# v001.net
KiCad netlist of a schematic drawn in EAGLE
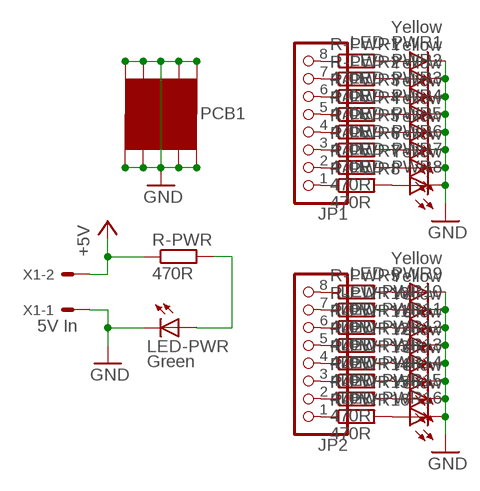
[diagram p0: schematic, sheet 1]

(export (version "E")
  (design (tool "Eeschema 10.0.6"))
  (components
    (comp (ref "JP1")
      (value "PINHD-1X8")
      (footprint "eagle-import:1X08")
      (libsource (lib "eagle-import") (part "PINHD-1X8"))
    )
    (comp (ref "JP2")
      (value "PINHD-1X8")
      (footprint "eagle-import:1X08")
      (libsource (lib "eagle-import") (part "PINHD-1X8"))
    )
    (comp (ref "LED-PWR")
      (value "Green")
      (footprint "eagle-import:LED3MM")
      (libsource (lib "eagle-import") (part "LED3MM"))
    )
    (comp (ref "LED-PWR1")
      (value "Yellow")
      (footprint "eagle-import:LED3MM")
      (libsource (lib "eagle-import") (part "LED3MM"))
    )
    (comp (ref "LED-PWR2")
      (value "Yellow")
      (footprint "eagle-import:LED3MM")
      (libsource (lib "eagle-import") (part "LED3MM"))
    )
    (comp (ref "LED-PWR3")
      (value "Yellow")
      (footprint "eagle-import:LED3MM")
      (libsource (lib "eagle-import") (part "LED3MM"))
    )
    (comp (ref "LED-PWR4")
      (value "Yellow")
      (footprint "eagle-import:LED3MM")
      (libsource (lib "eagle-import") (part "LED3MM"))
    )
    (comp (ref "LED-PWR5")
      (value "Yellow")
      (footprint "eagle-import:LED3MM")
      (libsource (lib "eagle-import") (part "LED3MM"))
    )
    (comp (ref "LED-PWR6")
      (value "Yellow")
      (footprint "eagle-import:LED3MM")
      (libsource (lib "eagle-import") (part "LED3MM"))
    )
    (comp (ref "LED-PWR7")
      (value "Yellow")
      (footprint "eagle-import:LED3MM")
      (libsource (lib "eagle-import") (part "LED3MM"))
    )
    (comp (ref "LED-PWR8")
      (value "Yellow")
      (footprint "eagle-import:LED3MM")
      (libsource (lib "eagle-import") (part "LED3MM"))
    )
    (comp (ref "LED-PWR9")
      (value "Yellow")
      (footprint "eagle-import:LED3MM")
      (libsource (lib "eagle-import") (part "LED3MM"))
    )
    (comp (ref "LED-PWR10")
      (value "Yellow")
      (footprint "eagle-import:LED3MM")
      (libsource (lib "eagle-import") (part "LED3MM"))
    )
    (comp (ref "LED-PWR11")
      (value "Yellow")
      (footprint "eagle-import:LED3MM")
      (libsource (lib "eagle-import") (part "LED3MM"))
    )
    (comp (ref "LED-PWR12")
      (value "Yellow")
      (footprint "eagle-import:LED3MM")
      (libsource (lib "eagle-import") (part "LED3MM"))
    )
    (comp (ref "LED-PWR13")
      (value "Yellow")
      (footprint "eagle-import:LED3MM")
      (libsource (lib "eagle-import") (part "LED3MM"))
    )
    (comp (ref "LED-PWR14")
      (value "Yellow")
      (footprint "eagle-import:LED3MM")
      (libsource (lib "eagle-import") (part "LED3MM"))
    )
    (comp (ref "LED-PWR15")
      (value "Yellow")
      (footprint "eagle-import:LED3MM")
      (libsource (lib "eagle-import") (part "LED3MM"))
    )
    (comp (ref "LED-PWR16")
      (value "Yellow")
      (footprint "eagle-import:LED3MM")
      (libsource (lib "eagle-import") (part "LED3MM"))
    )
    (comp (ref "PCB1")
      (value "PCB05X05")
      (footprint "eagle-import:PCB_05X05")
      (libsource (lib "eagle-import") (part "PCB05X05"))
    )
    (comp (ref "R-PWR")
      (value "470R")
      (footprint "eagle-import:0204_7")
      (libsource (lib "eagle-import") (part "R-EU_0204/7"))
    )
    (comp (ref "R-PWR1")
      (value "470R")
      (footprint "eagle-import:0204_7")
      (libsource (lib "eagle-import") (part "R-EU_0204/7"))
    )
    (comp (ref "R-PWR2")
      (value "470R")
      (footprint "eagle-import:0204_7")
      (libsource (lib "eagle-import") (part "R-EU_0204/7"))
    )
    (comp (ref "R-PWR3")
      (value "470R")
      (footprint "eagle-import:0204_7")
      (libsource (lib "eagle-import") (part "R-EU_0204/7"))
    )
    (comp (ref "R-PWR4")
      (value "470R")
      (footprint "eagle-import:0204_7")
      (libsource (lib "eagle-import") (part "R-EU_0204/7"))
    )
    (comp (ref "R-PWR5")
      (value "470R")
      (footprint "eagle-import:0204_7")
      (libsource (lib "eagle-import") (part "R-EU_0204/7"))
    )
    (comp (ref "R-PWR6")
      (value "470R")
      (footprint "eagle-import:0204_7")
      (libsource (lib "eagle-import") (part "R-EU_0204/7"))
    )
    (comp (ref "R-PWR7")
      (value "470R")
      (footprint "eagle-import:0204_7")
      (libsource (lib "eagle-import") (part "R-EU_0204/7"))
    )
    (comp (ref "R-PWR8")
      (value "470R")
      (footprint "eagle-import:0204_7")
      (libsource (lib "eagle-import") (part "R-EU_0204/7"))
    )
    (comp (ref "R-PWR9")
      (value "470R")
      (footprint "eagle-import:0204_7")
      (libsource (lib "eagle-import") (part "R-EU_0204/7"))
    )
    (comp (ref "R-PWR10")
      (value "470R")
      (footprint "eagle-import:0204_7")
      (libsource (lib "eagle-import") (part "R-EU_0204/7"))
    )
    (comp (ref "R-PWR11")
      (value "470R")
      (footprint "eagle-import:0204_7")
      (libsource (lib "eagle-import") (part "R-EU_0204/7"))
    )
    (comp (ref "R-PWR12")
      (value "470R")
      (footprint "eagle-import:0204_7")
      (libsource (lib "eagle-import") (part "R-EU_0204/7"))
    )
    (comp (ref "R-PWR13")
      (value "470R")
      (footprint "eagle-import:0204_7")
      (libsource (lib "eagle-import") (part "R-EU_0204/7"))
    )
    (comp (ref "R-PWR14")
      (value "470R")
      (footprint "eagle-import:0204_7")
      (libsource (lib "eagle-import") (part "R-EU_0204/7"))
    )
    (comp (ref "R-PWR15")
      (value "470R")
      (footprint "eagle-import:0204_7")
      (libsource (lib "eagle-import") (part "R-EU_0204/7"))
    )
    (comp (ref "R-PWR16")
      (value "470R")
      (footprint "eagle-import:0204_7")
      (libsource (lib "eagle-import") (part "R-EU_0204/7"))
    )
    (comp (ref "X1")
      (value "5V In")
      (footprint "eagle-import:6410-02")
      (libsource (lib "eagle-import") (part "22-?-0227-2021"))
    )
  )
  (nets
    (net (code "1") (name "+5V") (class "Default")
      (node (ref "R-PWR") (pin "1") (pinfunction "1_1") (pintype "passive"))
      (node (ref "X1") (pin "2") (pinfunction "S_2") (pintype "passive"))
    )
    (net (code "2") (name "GND") (class "Default")
      (node (ref "LED-PWR") (pin "K") (pinfunction "C_K") (pintype "passive"))
      (node (ref "LED-PWR1") (pin "K") (pinfunction "C_K") (pintype "passive"))
      (node (ref "LED-PWR10") (pin "K") (pinfunction "C_K") (pintype "passive"))
      (node (ref "LED-PWR11") (pin "K") (pinfunction "C_K") (pintype "passive"))
      (node (ref "LED-PWR12") (pin "K") (pinfunction "C_K") (pintype "passive"))
      (node (ref "LED-PWR13") (pin "K") (pinfunction "C_K") (pintype "passive"))
      (node (ref "LED-PWR14") (pin "K") (pinfunction "C_K") (pintype "passive"))
      (node (ref "LED-PWR15") (pin "K") (pinfunction "C_K") (pintype "passive"))
      (node (ref "LED-PWR16") (pin "K") (pinfunction "C_K") (pintype "passive"))
      (node (ref "LED-PWR2") (pin "K") (pinfunction "C_K") (pintype "passive"))
      (node (ref "LED-PWR3") (pin "K") (pinfunction "C_K") (pintype "passive"))
      (node (ref "LED-PWR4") (pin "K") (pinfunction "C_K") (pintype "passive"))
      (node (ref "LED-PWR5") (pin "K") (pinfunction "C_K") (pintype "passive"))
      (node (ref "LED-PWR6") (pin "K") (pinfunction "C_K") (pintype "passive"))
      (node (ref "LED-PWR7") (pin "K") (pinfunction "C_K") (pintype "passive"))
      (node (ref "LED-PWR8") (pin "K") (pinfunction "C_K") (pintype "passive"))
      (node (ref "LED-PWR9") (pin "K") (pinfunction "C_K") (pintype "passive"))
      (node (ref "PCB1") (pin "GND@1") (pinfunction "GND_GND@1") (pintype "bidirectional"))
      (node (ref "PCB1") (pin "GND@2") (pinfunction "GND_GND@2") (pintype "bidirectional"))
      (node (ref "PCB1") (pin "GND@3") (pinfunction "GND_GND@3") (pintype "bidirectional"))
      (node (ref "PCB1") (pin "GND@4") (pinfunction "GND_GND@4") (pintype "bidirectional"))
      (node (ref "PCB1") (pin "GND@5") (pinfunction "GND_GND@5") (pintype "bidirectional"))
      (node (ref "PCB1") (pin "GND@6") (pinfunction "GND_GND@6") (pintype "bidirectional"))
      (node (ref "PCB1") (pin "GND@7") (pinfunction "GND_GND@7") (pintype "bidirectional"))
      (node (ref "PCB1") (pin "GND@8") (pinfunction "GND_GND@8") (pintype "bidirectional"))
      (node (ref "X1") (pin "1") (pinfunction "S_1") (pintype "passive"))
    )
    (net (code "3") (name "Net-(JP1-Pad1)") (class "Default")
      (node (ref "JP1") (pin "1") (pinfunction "1_1") (pintype "passive"))
      (node (ref "R-PWR8") (pin "1") (pinfunction "1_1") (pintype "passive"))
    )
    (net (code "4") (name "Net-(JP1-Pad2)") (class "Default")
      (node (ref "JP1") (pin "2") (pinfunction "2_2") (pintype "passive"))
      (node (ref "R-PWR7") (pin "1") (pinfunction "1_1") (pintype "passive"))
    )
    (net (code "5") (name "Net-(JP1-Pad3)") (class "Default")
      (node (ref "JP1") (pin "3") (pinfunction "3_3") (pintype "passive"))
      (node (ref "R-PWR6") (pin "1") (pinfunction "1_1") (pintype "passive"))
    )
    (net (code "6") (name "Net-(JP1-Pad4)") (class "Default")
      (node (ref "JP1") (pin "4") (pinfunction "4_4") (pintype "passive"))
      (node (ref "R-PWR5") (pin "1") (pinfunction "1_1") (pintype "passive"))
    )
    (net (code "7") (name "Net-(JP1-Pad5)") (class "Default")
      (node (ref "JP1") (pin "5") (pinfunction "5_5") (pintype "passive"))
      (node (ref "R-PWR4") (pin "1") (pinfunction "1_1") (pintype "passive"))
    )
    (net (code "8") (name "Net-(JP1-Pad6)") (class "Default")
      (node (ref "JP1") (pin "6") (pinfunction "6_6") (pintype "passive"))
      (node (ref "R-PWR3") (pin "1") (pinfunction "1_1") (pintype "passive"))
    )
    (net (code "9") (name "Net-(JP1-Pad7)") (class "Default")
      (node (ref "JP1") (pin "7") (pinfunction "7_7") (pintype "passive"))
      (node (ref "R-PWR2") (pin "1") (pinfunction "1_1") (pintype "passive"))
    )
    (net (code "10") (name "Net-(JP1-Pad8)") (class "Default")
      (node (ref "JP1") (pin "8") (pinfunction "8_8") (pintype "passive"))
      (node (ref "R-PWR1") (pin "1") (pinfunction "1_1") (pintype "passive"))
    )
    (net (code "11") (name "Net-(JP2-Pad1)") (class "Default")
      (node (ref "JP2") (pin "1") (pinfunction "1_1") (pintype "passive"))
      (node (ref "R-PWR16") (pin "1") (pinfunction "1_1") (pintype "passive"))
    )
    (net (code "12") (name "Net-(JP2-Pad2)") (class "Default")
      (node (ref "JP2") (pin "2") (pinfunction "2_2") (pintype "passive"))
      (node (ref "R-PWR15") (pin "1") (pinfunction "1_1") (pintype "passive"))
    )
    (net (code "13") (name "Net-(JP2-Pad3)") (class "Default")
      (node (ref "JP2") (pin "3") (pinfunction "3_3") (pintype "passive"))
      (node (ref "R-PWR14") (pin "1") (pinfunction "1_1") (pintype "passive"))
    )
    (net (code "14") (name "Net-(JP2-Pad4)") (class "Default")
      (node (ref "JP2") (pin "4") (pinfunction "4_4") (pintype "passive"))
      (node (ref "R-PWR13") (pin "1") (pinfunction "1_1") (pintype "passive"))
    )
    (net (code "15") (name "Net-(JP2-Pad5)") (class "Default")
      (node (ref "JP2") (pin "5") (pinfunction "5_5") (pintype "passive"))
      (node (ref "R-PWR12") (pin "1") (pinfunction "1_1") (pintype "passive"))
    )
    (net (code "16") (name "Net-(JP2-Pad6)") (class "Default")
      (node (ref "JP2") (pin "6") (pinfunction "6_6") (pintype "passive"))
      (node (ref "R-PWR11") (pin "1") (pinfunction "1_1") (pintype "passive"))
    )
    (net (code "17") (name "Net-(JP2-Pad7)") (class "Default")
      (node (ref "JP2") (pin "7") (pinfunction "7_7") (pintype "passive"))
      (node (ref "R-PWR10") (pin "1") (pinfunction "1_1") (pintype "passive"))
    )
    (net (code "18") (name "Net-(JP2-Pad8)") (class "Default")
      (node (ref "JP2") (pin "8") (pinfunction "8_8") (pintype "passive"))
      (node (ref "R-PWR9") (pin "1") (pinfunction "1_1") (pintype "passive"))
    )
    (net (code "19") (name "Net-(LED-PWR-PadA)") (class "Default")
      (node (ref "LED-PWR") (pin "A") (pinfunction "A_A") (pintype "passive"))
      (node (ref "R-PWR") (pin "2") (pinfunction "2_2") (pintype "passive"))
    )
    (net (code "20") (name "Net-(LED-PWR1-PadA)") (class "Default")
      (node (ref "LED-PWR1") (pin "A") (pinfunction "A_A") (pintype "passive"))
      (node (ref "R-PWR1") (pin "2") (pinfunction "2_2") (pintype "passive"))
    )
    (net (code "21") (name "Net-(LED-PWR2-PadA)") (class "Default")
      (node (ref "LED-PWR2") (pin "A") (pinfunction "A_A") (pintype "passive"))
      (node (ref "R-PWR2") (pin "2") (pinfunction "2_2") (pintype "passive"))
    )
    (net (code "22") (name "Net-(LED-PWR3-PadA)") (class "Default")
      (node (ref "LED-PWR3") (pin "A") (pinfunction "A_A") (pintype "passive"))
      (node (ref "R-PWR3") (pin "2") (pinfunction "2_2") (pintype "passive"))
    )
    (net (code "23") (name "Net-(LED-PWR4-PadA)") (class "Default")
      (node (ref "LED-PWR4") (pin "A") (pinfunction "A_A") (pintype "passive"))
      (node (ref "R-PWR4") (pin "2") (pinfunction "2_2") (pintype "passive"))
    )
    (net (code "24") (name "Net-(LED-PWR5-PadA)") (class "Default")
      (node (ref "LED-PWR5") (pin "A") (pinfunction "A_A") (pintype "passive"))
      (node (ref "R-PWR5") (pin "2") (pinfunction "2_2") (pintype "passive"))
    )
    (net (code "25") (name "Net-(LED-PWR6-PadA)") (class "Default")
      (node (ref "LED-PWR6") (pin "A") (pinfunction "A_A") (pintype "passive"))
      (node (ref "R-PWR6") (pin "2") (pinfunction "2_2") (pintype "passive"))
    )
    (net (code "26") (name "Net-(LED-PWR7-PadA)") (class "Default")
      (node (ref "LED-PWR7") (pin "A") (pinfunction "A_A") (pintype "passive"))
      (node (ref "R-PWR7") (pin "2") (pinfunction "2_2") (pintype "passive"))
    )
    (net (code "27") (name "Net-(LED-PWR8-PadA)") (class "Default")
      (node (ref "LED-PWR8") (pin "A") (pinfunction "A_A") (pintype "passive"))
      (node (ref "R-PWR8") (pin "2") (pinfunction "2_2") (pintype "passive"))
    )
    (net (code "28") (name "Net-(LED-PWR9-PadA)") (class "Default")
      (node (ref "LED-PWR9") (pin "A") (pinfunction "A_A") (pintype "passive"))
      (node (ref "R-PWR9") (pin "2") (pinfunction "2_2") (pintype "passive"))
    )
    (net (code "29") (name "Net-(LED-PWR10-PadA)") (class "Default")
      (node (ref "LED-PWR10") (pin "A") (pinfunction "A_A") (pintype "passive"))
      (node (ref "R-PWR10") (pin "2") (pinfunction "2_2") (pintype "passive"))
    )
    (net (code "30") (name "Net-(LED-PWR11-PadA)") (class "Default")
      (node (ref "LED-PWR11") (pin "A") (pinfunction "A_A") (pintype "passive"))
      (node (ref "R-PWR11") (pin "2") (pinfunction "2_2") (pintype "passive"))
    )
    (net (code "31") (name "Net-(LED-PWR12-PadA)") (class "Default")
      (node (ref "LED-PWR12") (pin "A") (pinfunction "A_A") (pintype "passive"))
      (node (ref "R-PWR12") (pin "2") (pinfunction "2_2") (pintype "passive"))
    )
    (net (code "32") (name "Net-(LED-PWR13-PadA)") (class "Default")
      (node (ref "LED-PWR13") (pin "A") (pinfunction "A_A") (pintype "passive"))
      (node (ref "R-PWR13") (pin "2") (pinfunction "2_2") (pintype "passive"))
    )
    (net (code "33") (name "Net-(LED-PWR14-PadA)") (class "Default")
      (node (ref "LED-PWR14") (pin "A") (pinfunction "A_A") (pintype "passive"))
      (node (ref "R-PWR14") (pin "2") (pinfunction "2_2") (pintype "passive"))
    )
    (net (code "34") (name "Net-(LED-PWR15-PadA)") (class "Default")
      (node (ref "LED-PWR15") (pin "A") (pinfunction "A_A") (pintype "passive"))
      (node (ref "R-PWR15") (pin "2") (pinfunction "2_2") (pintype "passive"))
    )
    (net (code "35") (name "Net-(LED-PWR16-PadA)") (class "Default")
      (node (ref "LED-PWR16") (pin "A") (pinfunction "A_A") (pintype "passive"))
      (node (ref "R-PWR16") (pin "2") (pinfunction "2_2") (pintype "passive"))
    )
  )
)
